# uProcesador.net
KiCad netlist of a schematic drawn in Altium Designer
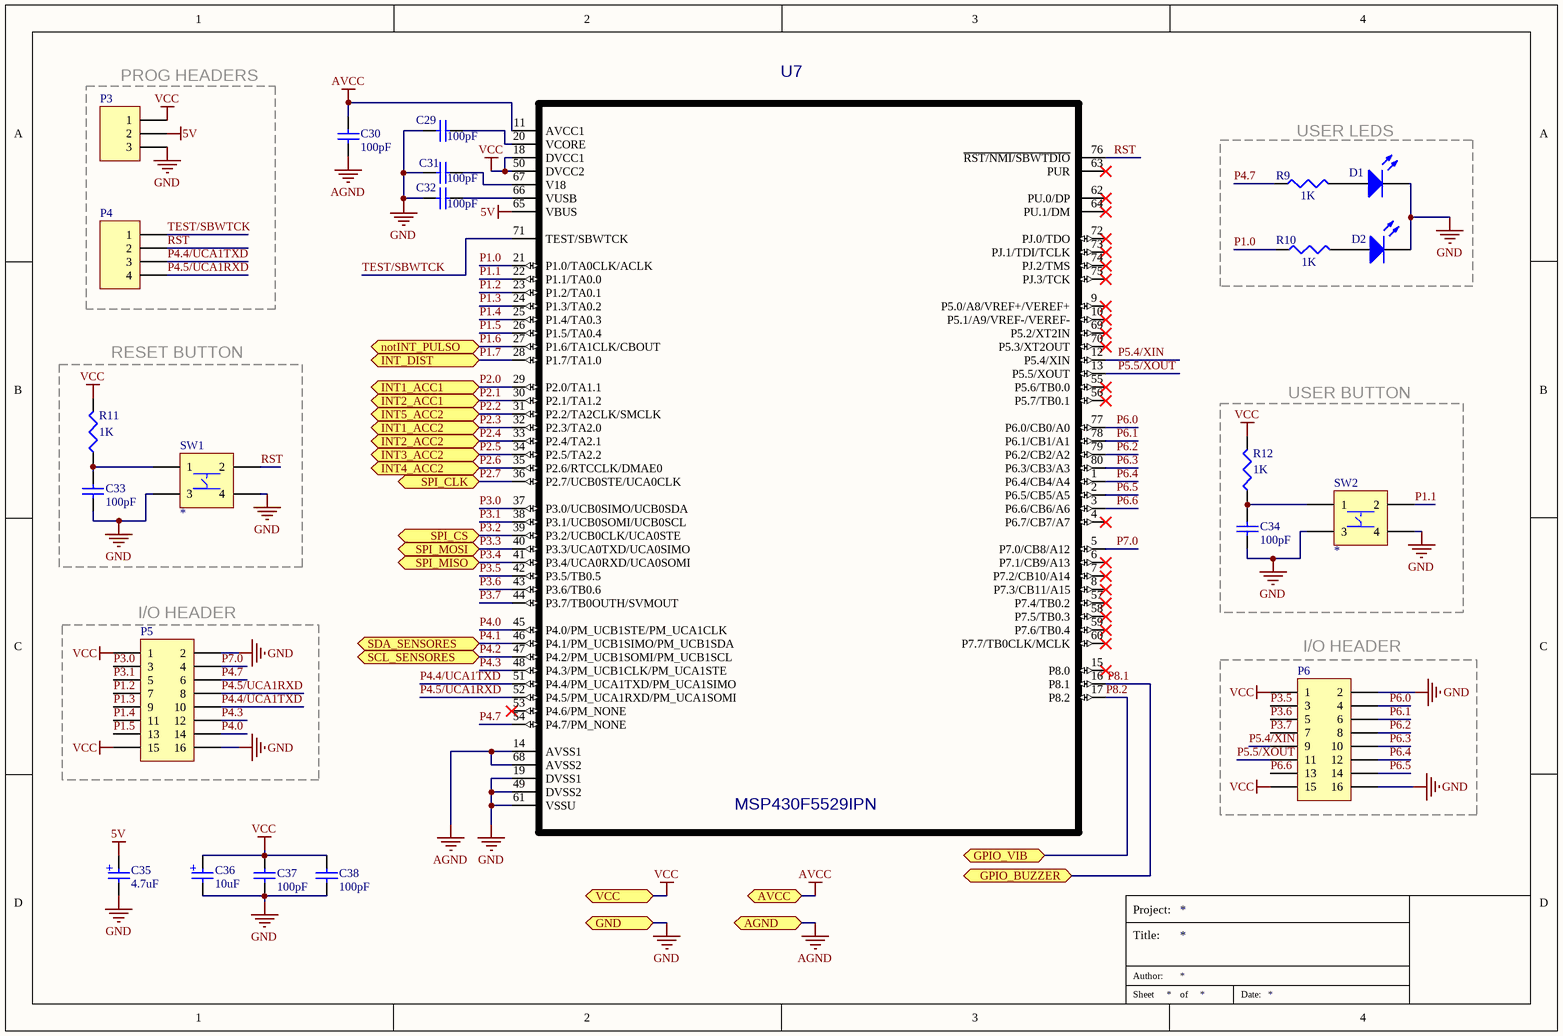
[diagram p0: uProcesador.SchDoc]

(export (version "E")
  (design (tool "Eeschema 10.0.6"))
  (components
    (comp (ref "C29")
      (value "100pF")
      (footprint "C1206")
      (description "Capacitor (Semiconductor SIM Model)")
      (fields (field (name "PUBLISHER") "Altium Limited"))
      (libsource (lib "Miscellaneous Devices") (part "Cap Semi"))
    )
    (comp (ref "C30")
      (value "100pF")
      (footprint "C1206")
      (description "Capacitor (Semiconductor SIM Model)")
      (fields (field (name "PUBLISHER") "Altium Limited"))
      (libsource (lib "Miscellaneous Devices") (part "Cap Semi"))
    )
    (comp (ref "C31")
      (value "100pF")
      (footprint "C1206")
      (description "Capacitor (Semiconductor SIM Model)")
      (fields (field (name "PUBLISHER") "Altium Limited"))
      (libsource (lib "Miscellaneous Devices") (part "Cap Semi"))
    )
    (comp (ref "C32")
      (value "100pF")
      (footprint "C1206")
      (description "Capacitor (Semiconductor SIM Model)")
      (fields (field (name "PUBLISHER") "Altium Limited"))
      (libsource (lib "Miscellaneous Devices") (part "Cap Semi"))
    )
    (comp (ref "C33")
      (value "100pF")
      (footprint "C1206")
      (description "Capacitor (Semiconductor SIM Model)")
      (fields (field (name "PUBLISHER") "Altium Limited"))
      (libsource (lib "Miscellaneous Devices") (part "Cap Semi"))
    )
    (comp (ref "C34")
      (value "100pF")
      (footprint "C1206")
      (description "Capacitor (Semiconductor SIM Model)")
      (fields (field (name "PUBLISHER") "Altium Limited"))
      (libsource (lib "Miscellaneous Devices") (part "Cap Semi"))
    )
    (comp (ref "C35")
      (value "4.7uF")
      (footprint "Cap Pol")
      (description "Capacitor pol")
      (fields (field (name "PUBLISHER") "Altium Limited"))
      (libsource (lib "Schematics") (part "Cap Pol"))
    )
    (comp (ref "C36")
      (value "10uF")
      (footprint "Cap Pol")
      (description "Capacitor pol")
      (fields (field (name "PUBLISHER") "Altium Limited"))
      (libsource (lib "Schematics") (part "Cap Pol"))
    )
    (comp (ref "C37")
      (value "100pF")
      (footprint "C1206")
      (description "Capacitor (Semiconductor SIM Model)")
      (fields (field (name "PUBLISHER") "Altium Limited"))
      (libsource (lib "Miscellaneous Devices") (part "Cap Semi"))
    )
    (comp (ref "C38")
      (value "100pF")
      (footprint "C1206")
      (description "Capacitor (Semiconductor SIM Model)")
      (fields (field (name "PUBLISHER") "Altium Limited"))
      (libsource (lib "Miscellaneous Devices") (part "Cap Semi"))
    )
    (comp (ref "D1")
      (value "~")
      (footprint "3.2X1.6X1.1")
      (description "Typical RED, GREEN, YELLOW, AMBER GaAs LED")
      (fields (field (name "PUBLISHER") "Altium Limited"))
      (libsource (lib "Miscellaneous Devices") (part "LED2"))
    )
    (comp (ref "D2")
      (value "~")
      (footprint "3.2X1.6X1.1")
      (description "Typical RED, GREEN, YELLOW, AMBER GaAs LED")
      (fields (field (name "PUBLISHER") "Altium Limited"))
      (libsource (lib "Miscellaneous Devices") (part "LED2"))
    )
    (comp (ref "P3")
      (value "~")
      (footprint "HDR1X3")
      (description "Header, 3-Pin")
      (fields (field (name "PUBLISHER") "Altium Limited"))
      (libsource (lib "Miscellaneous Connectors") (part "Header 3"))
    )
    (comp (ref "P4")
      (value "~")
      (footprint "HDR1X4")
      (description "Header, 4-Pin")
      (fields (field (name "PUBLISHER") "Altium Limited"))
      (libsource (lib "Miscellaneous Connectors") (part "Header 4"))
    )
    (comp (ref "P5")
      (value "~")
      (footprint "HDR2X8")
      (description "Header, 8-Pin, Dual row")
      (fields (field (name "PUBLISHER") "Altium Limited"))
      (libsource (lib "Miscellaneous Connectors") (part "Header 8X2"))
    )
    (comp (ref "P6")
      (value "~")
      (footprint "HDR2X8")
      (description "Header, 8-Pin, Dual row")
      (fields (field (name "PUBLISHER") "Altium Limited"))
      (libsource (lib "Miscellaneous Connectors") (part "Header 8X2"))
    )
    (comp (ref "R9")
      (value "1K")
      (footprint "J1-0603")
      (description "Resistor")
      (fields (field (name "PUBLISHER") "Altium Limited"))
      (libsource (lib "Miscellaneous Devices") (part "Res3"))
    )
    (comp (ref "R10")
      (value "1K")
      (footprint "J1-0603")
      (description "Resistor")
      (fields (field (name "PUBLISHER") "Altium Limited"))
      (libsource (lib "Miscellaneous Devices") (part "Res3"))
    )
    (comp (ref "R11")
      (value "1K")
      (footprint "J1-0603")
      (description "Resistor")
      (fields (field (name "PUBLISHER") "Altium Limited"))
      (libsource (lib "Miscellaneous Devices") (part "Res3"))
    )
    (comp (ref "R12")
      (value "1K")
      (footprint "J1-0603")
      (description "Resistor")
      (fields (field (name "PUBLISHER") "Altium Limited"))
      (libsource (lib "Miscellaneous Devices") (part "Res3"))
    )
    (comp (ref "SW1") (value "*") (footprint "CKN9085CT") (libsource (lib "Schematics") (part "CKN9085CT")))
    (comp (ref "SW2") (value "*") (footprint "CKN9085CT") (libsource (lib "Schematics") (part "CKN9085CT")))
    (comp (ref "U7")
      (value "MSP430F5529IPN")
      (footprint "QFP50P1400X1400X160-80N")
      (fields (field (name "MF") "Texas Instruments"))
      (libsource (lib "Schematics") (part "MSP430F5529IPN"))
    )
  )
  (nets
    (net (code "1") (name "/P1.0") (class "Default")
      (node (ref "R10") (pin "1") (pinfunction "1_1") (pintype "passive"))
      (node (ref "U7") (pin "21") (pinfunction "P1.0/TA0CLK/ACLK_21") (pintype "bidirectional"))
    )
    (net (code "2") (name "/P1.1") (class "Default")
      (node (ref "SW2") (pin "2") (pinfunction "2_2") (pintype "passive"))
      (node (ref "U7") (pin "22") (pinfunction "P1.1/TA0.0_22") (pintype "bidirectional"))
    )
    (net (code "3") (name "/P1.2") (class "Default")
      (node (ref "P5") (pin "7") (pinfunction "7_7") (pintype "passive"))
      (node (ref "U7") (pin "23") (pinfunction "P1.2/TA0.1_23") (pintype "bidirectional"))
    )
    (net (code "4") (name "/P1.3") (class "Default")
      (node (ref "P5") (pin "9") (pinfunction "9_9") (pintype "passive"))
      (node (ref "U7") (pin "24") (pinfunction "P1.3/TA0.2_24") (pintype "bidirectional"))
    )
    (net (code "5") (name "/P1.4") (class "Default")
      (node (ref "P5") (pin "11") (pinfunction "11_11") (pintype "passive"))
      (node (ref "U7") (pin "25") (pinfunction "P1.4/TA0.3_25") (pintype "bidirectional"))
    )
    (net (code "6") (name "/P1.5") (class "Default")
      (node (ref "P5") (pin "13") (pinfunction "13_13") (pintype "passive"))
      (node (ref "U7") (pin "26") (pinfunction "P1.5/TA0.4_26") (pintype "bidirectional"))
    )
    (net (code "7") (name "/P1.6") (class "Default")
      (node (ref "U7") (pin "27") (pinfunction "P1.6/TA1CLK/CBOUT_27") (pintype "bidirectional"))
    )
    (net (code "8") (name "/P1.7") (class "Default")
      (node (ref "U7") (pin "28") (pinfunction "P1.7/TA1.0_28") (pintype "bidirectional"))
    )
    (net (code "9") (name "/P2.0") (class "Default")
      (node (ref "U7") (pin "29") (pinfunction "P2.0/TA1.1_29") (pintype "bidirectional"))
    )
    (net (code "10") (name "/P2.1") (class "Default")
      (node (ref "U7") (pin "30") (pinfunction "P2.1/TA1.2_30") (pintype "bidirectional"))
    )
    (net (code "11") (name "/P2.2") (class "Default")
      (node (ref "U7") (pin "31") (pinfunction "P2.2/TA2CLK/SMCLK_31") (pintype "bidirectional"))
    )
    (net (code "12") (name "/P2.3") (class "Default")
      (node (ref "U7") (pin "32") (pinfunction "P2.3/TA2.0_32") (pintype "bidirectional"))
    )
    (net (code "13") (name "/P2.4") (class "Default")
      (node (ref "U7") (pin "33") (pinfunction "P2.4/TA2.1_33") (pintype "bidirectional"))
    )
    (net (code "14") (name "/P2.5") (class "Default")
      (node (ref "U7") (pin "34") (pinfunction "P2.5/TA2.2_34") (pintype "bidirectional"))
    )
    (net (code "15") (name "/P2.6") (class "Default")
      (node (ref "U7") (pin "35") (pinfunction "P2.6/RTCCLK/DMAE0_35") (pintype "bidirectional"))
    )
    (net (code "16") (name "/P2.7") (class "Default")
      (node (ref "U7") (pin "36") (pinfunction "P2.7/UCB0STE/UCA0CLK_36") (pintype "bidirectional"))
    )
    (net (code "17") (name "/P3.0") (class "Default")
      (node (ref "P5") (pin "3") (pinfunction "3_3") (pintype "passive"))
      (node (ref "U7") (pin "37") (pinfunction "P3.0/UCB0SIMO/UCB0SDA_37") (pintype "bidirectional"))
    )
    (net (code "18") (name "/P3.1") (class "Default")
      (node (ref "P5") (pin "5") (pinfunction "5_5") (pintype "passive"))
      (node (ref "U7") (pin "38") (pinfunction "P3.1/UCB0SOMI/UCB0SCL_38") (pintype "bidirectional"))
    )
    (net (code "19") (name "/P3.2") (class "Default")
      (node (ref "U7") (pin "39") (pinfunction "P3.2/UCB0CLK/UCA0STE_39") (pintype "bidirectional"))
    )
    (net (code "20") (name "/P3.3") (class "Default")
      (node (ref "U7") (pin "40") (pinfunction "P3.3/UCA0TXD/UCA0SIMO_40") (pintype "bidirectional"))
    )
    (net (code "21") (name "/P3.4") (class "Default")
      (node (ref "U7") (pin "41") (pinfunction "P3.4/UCA0RXD/UCA0SOMI_41") (pintype "bidirectional"))
    )
    (net (code "22") (name "/P3.5") (class "Default")
      (node (ref "P6") (pin "3") (pinfunction "3_3") (pintype "passive"))
      (node (ref "U7") (pin "42") (pinfunction "P3.5/TB0.5_42") (pintype "bidirectional"))
    )
    (net (code "23") (name "/P3.6") (class "Default")
      (node (ref "P6") (pin "5") (pinfunction "5_5") (pintype "passive"))
      (node (ref "U7") (pin "43") (pinfunction "P3.6/TB0.6_43") (pintype "bidirectional"))
    )
    (net (code "24") (name "/P3.7") (class "Default")
      (node (ref "P6") (pin "7") (pinfunction "7_7") (pintype "passive"))
      (node (ref "U7") (pin "44") (pinfunction "P3.7/TB0OUTH/SVMOUT_44") (pintype "bidirectional"))
    )
    (net (code "25") (name "/P4.0") (class "Default")
      (node (ref "P5") (pin "14") (pinfunction "14_14") (pintype "passive"))
      (node (ref "U7") (pin "45") (pinfunction "P4.0/PM_UCB1STE/PM_UCA1CLK_45") (pintype "bidirectional"))
    )
    (net (code "26") (name "/P4.1") (class "Default")
      (node (ref "U7") (pin "46") (pinfunction "P4.1/PM_UCB1SIMO/PM_UCB1SDA_46") (pintype "bidirectional"))
    )
    (net (code "27") (name "/P4.2") (class "Default")
      (node (ref "U7") (pin "47") (pinfunction "P4.2/PM_UCB1SOMI/PM_UCB1SCL_47") (pintype "bidirectional"))
    )
    (net (code "28") (name "/P4.3") (class "Default")
      (node (ref "P5") (pin "12") (pinfunction "12_12") (pintype "passive"))
      (node (ref "U7") (pin "48") (pinfunction "P4.3/PM_UCB1CLK/PM_UCA1STE_48") (pintype "bidirectional"))
    )
    (net (code "29") (name "/P4.4{slash}UCA1TXD") (class "Default")
      (node (ref "P4") (pin "3") (pinfunction "3_3") (pintype "passive"))
      (node (ref "P5") (pin "10") (pinfunction "10_10") (pintype "passive"))
      (node (ref "U7") (pin "51") (pinfunction "P4.4/PM_UCA1TXD/PM_UCA1SIMO_51") (pintype "bidirectional"))
    )
    (net (code "30") (name "/P4.5{slash}UCA1RXD") (class "Default")
      (node (ref "P4") (pin "4") (pinfunction "4_4") (pintype "passive"))
      (node (ref "P5") (pin "8") (pinfunction "8_8") (pintype "passive"))
      (node (ref "U7") (pin "52") (pinfunction "P4.5/PM_UCA1RXD/PM_UCA1SOMI_52") (pintype "bidirectional"))
    )
    (net (code "31") (name "/P4.7") (class "Default")
      (node (ref "P5") (pin "6") (pinfunction "6_6") (pintype "passive"))
      (node (ref "R9") (pin "1") (pinfunction "1_1") (pintype "passive"))
      (node (ref "U7") (pin "54") (pinfunction "P4.7/PM_NONE_54") (pintype "bidirectional"))
    )
    (net (code "32") (name "/P5.4{slash}XIN") (class "Default")
      (node (ref "P6") (pin "9") (pinfunction "9_9") (pintype "passive"))
      (node (ref "U7") (pin "12") (pinfunction "P5.4/XIN_12") (pintype "bidirectional"))
    )
    (net (code "33") (name "/P5.5{slash}XOUT") (class "Default")
      (node (ref "P6") (pin "11") (pinfunction "11_11") (pintype "passive"))
      (node (ref "U7") (pin "13") (pinfunction "P5.5/XOUT_13") (pintype "bidirectional"))
    )
    (net (code "34") (name "/P6.0") (class "Default")
      (node (ref "P6") (pin "4") (pinfunction "4_4") (pintype "passive"))
      (node (ref "U7") (pin "77") (pinfunction "P6.0/CB0/A0_77") (pintype "bidirectional"))
    )
    (net (code "35") (name "/P6.1") (class "Default")
      (node (ref "P6") (pin "6") (pinfunction "6_6") (pintype "passive"))
      (node (ref "U7") (pin "78") (pinfunction "P6.1/CB1/A1_78") (pintype "bidirectional"))
    )
    (net (code "36") (name "/P6.2") (class "Default")
      (node (ref "P6") (pin "8") (pinfunction "8_8") (pintype "passive"))
      (node (ref "U7") (pin "79") (pinfunction "P6.2/CB2/A2_79") (pintype "bidirectional"))
    )
    (net (code "37") (name "/P6.3") (class "Default")
      (node (ref "P6") (pin "10") (pinfunction "10_10") (pintype "passive"))
      (node (ref "U7") (pin "80") (pinfunction "P6.3/CB3/A3_80") (pintype "bidirectional"))
    )
    (net (code "38") (name "/P6.4") (class "Default")
      (node (ref "P6") (pin "12") (pinfunction "12_12") (pintype "passive"))
      (node (ref "U7") (pin "1") (pinfunction "P6.4/CB4/A4_1") (pintype "bidirectional"))
    )
    (net (code "39") (name "/P6.5") (class "Default")
      (node (ref "P6") (pin "14") (pinfunction "14_14") (pintype "passive"))
      (node (ref "U7") (pin "2") (pinfunction "P6.5/CB5/A5_2") (pintype "bidirectional"))
    )
    (net (code "40") (name "/P6.6") (class "Default")
      (node (ref "P6") (pin "13") (pinfunction "13_13") (pintype "passive"))
      (node (ref "U7") (pin "3") (pinfunction "P6.6/CB6/A6_3") (pintype "bidirectional"))
    )
    (net (code "41") (name "/P7.0") (class "Default")
      (node (ref "P5") (pin "4") (pinfunction "4_4") (pintype "passive"))
      (node (ref "U7") (pin "5") (pinfunction "P7.0/CB8/A12_5") (pintype "bidirectional"))
    )
    (net (code "42") (name "/P8.1") (class "Default")
      (node (ref "U7") (pin "16") (pinfunction "P8.1_16") (pintype "bidirectional"))
    )
    (net (code "43") (name "/P8.2") (class "Default")
      (node (ref "U7") (pin "17") (pinfunction "P8.2_17") (pintype "bidirectional"))
    )
    (net (code "44") (name "/RST") (class "Default")
      (node (ref "P4") (pin "2") (pinfunction "2_2") (pintype "passive"))
      (node (ref "SW1") (pin "2") (pinfunction "2_2") (pintype "passive"))
      (node (ref "U7") (pin "76") (pinfunction "~{RST/NMI/SBWTDIO}_76") (pintype "passive"))
    )
    (net (code "45") (name "/TEST{slash}SBWTCK") (class "Default")
      (node (ref "P4") (pin "1") (pinfunction "1_1") (pintype "passive"))
      (node (ref "U7") (pin "71") (pinfunction "TEST/SBWTCK_71") (pintype "passive"))
    )
    (net (code "46") (name "5V") (class "Default")
      (node (ref "C35") (pin "2") (pinfunction "2_2") (pintype "passive"))
      (node (ref "P3") (pin "2") (pinfunction "2_2") (pintype "passive"))
      (node (ref "U7") (pin "65") (pinfunction "VBUS_65") (pintype "passive"))
    )
    (net (code "47") (name "AGND") (class "Default")
      (node (ref "C30") (pin "1") (pinfunction "1_1") (pintype "passive"))
      (node (ref "U7") (pin "14") (pinfunction "AVSS1_14") (pintype "power_in"))
      (node (ref "U7") (pin "68") (pinfunction "AVSS2_68") (pintype "power_in"))
    )
    (net (code "48") (name "AVCC") (class "Default")
      (node (ref "C30") (pin "2") (pinfunction "2_2") (pintype "passive"))
      (node (ref "U7") (pin "11") (pinfunction "AVCC1_11") (pintype "power_in"))
    )
    (net (code "49") (name "GND") (class "Default")
      (node (ref "C29") (pin "2") (pinfunction "2_2") (pintype "passive"))
      (node (ref "C31") (pin "2") (pinfunction "2_2") (pintype "passive"))
      (node (ref "C32") (pin "2") (pinfunction "2_2") (pintype "passive"))
      (node (ref "C33") (pin "1") (pinfunction "1_1") (pintype "passive"))
      (node (ref "C34") (pin "1") (pinfunction "1_1") (pintype "passive"))
      (node (ref "C35") (pin "1") (pinfunction "1_1") (pintype "passive"))
      (node (ref "C36") (pin "1") (pinfunction "1_1") (pintype "passive"))
      (node (ref "C37") (pin "1") (pinfunction "1_1") (pintype "passive"))
      (node (ref "C38") (pin "1") (pinfunction "1_1") (pintype "passive"))
      (node (ref "D1") (pin "2") (pinfunction "K_2") (pintype "passive"))
      (node (ref "D2") (pin "2") (pinfunction "K_2") (pintype "passive"))
      (node (ref "P3") (pin "3") (pinfunction "3_3") (pintype "passive"))
      (node (ref "P5") (pin "16") (pinfunction "16_16") (pintype "passive"))
      (node (ref "P5") (pin "2") (pinfunction "2_2") (pintype "passive"))
      (node (ref "P6") (pin "16") (pinfunction "16_16") (pintype "passive"))
      (node (ref "P6") (pin "2") (pinfunction "2_2") (pintype "passive"))
      (node (ref "SW1") (pin "3") (pinfunction "3_3") (pintype "passive"))
      (node (ref "SW1") (pin "4") (pinfunction "4_4") (pintype "passive"))
      (node (ref "SW2") (pin "3") (pinfunction "3_3") (pintype "passive"))
      (node (ref "SW2") (pin "4") (pinfunction "4_4") (pintype "passive"))
      (node (ref "U7") (pin "19") (pinfunction "DVSS1_19") (pintype "power_in"))
      (node (ref "U7") (pin "49") (pinfunction "DVSS2_49") (pintype "power_in"))
      (node (ref "U7") (pin "61") (pinfunction "VSSU_61") (pintype "power_in"))
    )
    (net (code "50") (name "Net-(C33-Pad2)") (class "Default")
      (node (ref "C33") (pin "2") (pinfunction "2_2") (pintype "passive"))
      (node (ref "R11") (pin "1") (pinfunction "1_1") (pintype "passive"))
      (node (ref "SW1") (pin "1") (pinfunction "1_1") (pintype "passive"))
    )
    (net (code "51") (name "Net-(C34-Pad2)") (class "Default")
      (node (ref "C34") (pin "2") (pinfunction "2_2") (pintype "passive"))
      (node (ref "R12") (pin "1") (pinfunction "1_1") (pintype "passive"))
      (node (ref "SW2") (pin "1") (pinfunction "1_1") (pintype "passive"))
    )
    (net (code "52") (name "Net-(D1-A)") (class "Default")
      (node (ref "D1") (pin "1") (pinfunction "A_1") (pintype "passive"))
      (node (ref "R9") (pin "2") (pinfunction "2_2") (pintype "passive"))
    )
    (net (code "53") (name "Net-(D2-A)") (class "Default")
      (node (ref "D2") (pin "1") (pinfunction "A_1") (pintype "passive"))
      (node (ref "R10") (pin "2") (pinfunction "2_2") (pintype "passive"))
    )
    (net (code "54") (name "Net-(U7-V18)") (class "Default")
      (node (ref "C31") (pin "1") (pinfunction "1_1") (pintype "passive"))
      (node (ref "U7") (pin "67") (pinfunction "V18_67") (pintype "passive"))
    )
    (net (code "55") (name "Net-(U7-VCORE)") (class "Default")
      (node (ref "C29") (pin "1") (pinfunction "1_1") (pintype "passive"))
      (node (ref "U7") (pin "20") (pinfunction "VCORE_20") (pintype "passive"))
    )
    (net (code "56") (name "Net-(U7-VUSB)") (class "Default")
      (node (ref "C32") (pin "1") (pinfunction "1_1") (pintype "passive"))
      (node (ref "U7") (pin "66") (pinfunction "VUSB_66") (pintype "passive"))
    )
    (net (code "57") (name "VCC") (class "Default")
      (node (ref "C36") (pin "2") (pinfunction "2_2") (pintype "passive"))
      (node (ref "C37") (pin "2") (pinfunction "2_2") (pintype "passive"))
      (node (ref "C38") (pin "2") (pinfunction "2_2") (pintype "passive"))
      (node (ref "P3") (pin "1") (pinfunction "1_1") (pintype "passive"))
      (node (ref "P5") (pin "1") (pinfunction "1_1") (pintype "passive"))
      (node (ref "P5") (pin "15") (pinfunction "15_15") (pintype "passive"))
      (node (ref "P6") (pin "1") (pinfunction "1_1") (pintype "passive"))
      (node (ref "P6") (pin "15") (pinfunction "15_15") (pintype "passive"))
      (node (ref "R11") (pin "2") (pinfunction "2_2") (pintype "passive"))
      (node (ref "R12") (pin "2") (pinfunction "2_2") (pintype "passive"))
      (node (ref "U7") (pin "18") (pinfunction "DVCC1_18") (pintype "power_in"))
      (node (ref "U7") (pin "50") (pinfunction "DVCC2_50") (pintype "power_in"))
    )
    (net (code "58") (name "unconnected-(U7-P4.6{slash}PM_NONE-Pad53)") (class "Default")
      (node (ref "U7") (pin "53") (pinfunction "P4.6/PM_NONE_53") (pintype "bidirectional+no_connect"))
    )
    (net (code "59") (name "unconnected-(U7-P5.0{slash}A8{slash}VREF+{slash}VEREF+-Pad9)") (class "Default")
      (node (ref "U7") (pin "9") (pinfunction "P5.0/A8/VREF+/VEREF+_9") (pintype "bidirectional+no_connect"))
    )
    (net (code "60") (name "unconnected-(U7-P5.1{slash}A9{slash}VREF-{slash}VEREF--Pad10)") (class "Default")
      (node (ref "U7") (pin "10") (pinfunction "P5.1/A9/VREF-/VEREF-_10") (pintype "bidirectional+no_connect"))
    )
    (net (code "61") (name "unconnected-(U7-P5.2{slash}XT2IN-Pad69)") (class "Default")
      (node (ref "U7") (pin "69") (pinfunction "P5.2/XT2IN_69") (pintype "bidirectional+no_connect"))
    )
    (net (code "62") (name "unconnected-(U7-P5.3{slash}XT2OUT-Pad70)") (class "Default")
      (node (ref "U7") (pin "70") (pinfunction "P5.3/XT2OUT_70") (pintype "bidirectional+no_connect"))
    )
    (net (code "63") (name "unconnected-(U7-P5.6{slash}TB0.0-Pad55)") (class "Default")
      (node (ref "U7") (pin "55") (pinfunction "P5.6/TB0.0_55") (pintype "bidirectional+no_connect"))
    )
    (net (code "64") (name "unconnected-(U7-P5.7{slash}TB0.1-Pad56)") (class "Default")
      (node (ref "U7") (pin "56") (pinfunction "P5.7/TB0.1_56") (pintype "bidirectional+no_connect"))
    )
    (net (code "65") (name "unconnected-(U7-P6.7{slash}CB7{slash}A7-Pad4)") (class "Default")
      (node (ref "U7") (pin "4") (pinfunction "P6.7/CB7/A7_4") (pintype "bidirectional+no_connect"))
    )
    (net (code "66") (name "unconnected-(U7-P7.1{slash}CB9{slash}A13-Pad6)") (class "Default")
      (node (ref "U7") (pin "6") (pinfunction "P7.1/CB9/A13_6") (pintype "bidirectional+no_connect"))
    )
    (net (code "67") (name "unconnected-(U7-P7.2{slash}CB10{slash}A14-Pad7)") (class "Default")
      (node (ref "U7") (pin "7") (pinfunction "P7.2/CB10/A14_7") (pintype "bidirectional+no_connect"))
    )
    (net (code "68") (name "unconnected-(U7-P7.3{slash}CB11{slash}A15-Pad8)") (class "Default")
      (node (ref "U7") (pin "8") (pinfunction "P7.3/CB11/A15_8") (pintype "bidirectional+no_connect"))
    )
    (net (code "69") (name "unconnected-(U7-P7.4{slash}TB0.2-Pad57)") (class "Default")
      (node (ref "U7") (pin "57") (pinfunction "P7.4/TB0.2_57") (pintype "bidirectional+no_connect"))
    )
    (net (code "70") (name "unconnected-(U7-P7.5{slash}TB0.3-Pad58)") (class "Default")
      (node (ref "U7") (pin "58") (pinfunction "P7.5/TB0.3_58") (pintype "bidirectional+no_connect"))
    )
    (net (code "71") (name "unconnected-(U7-P7.6{slash}TB0.4-Pad59)") (class "Default")
      (node (ref "U7") (pin "59") (pinfunction "P7.6/TB0.4_59") (pintype "bidirectional+no_connect"))
    )
    (net (code "72") (name "unconnected-(U7-P7.7{slash}TB0CLK{slash}MCLK-Pad60)") (class "Default")
      (node (ref "U7") (pin "60") (pinfunction "P7.7/TB0CLK/MCLK_60") (pintype "bidirectional+no_connect"))
    )
    (net (code "73") (name "unconnected-(U7-P8.0-Pad15)") (class "Default")
      (node (ref "U7") (pin "15") (pinfunction "P8.0_15") (pintype "bidirectional+no_connect"))
    )
    (net (code "74") (name "unconnected-(U7-PJ.0{slash}TDO-Pad72)") (class "Default")
      (node (ref "U7") (pin "72") (pinfunction "PJ.0/TDO_72") (pintype "bidirectional+no_connect"))
    )
    (net (code "75") (name "unconnected-(U7-PJ.1{slash}TDI{slash}TCLK-Pad73)") (class "Default")
      (node (ref "U7") (pin "73") (pinfunction "PJ.1/TDI/TCLK_73") (pintype "bidirectional+no_connect"))
    )
    (net (code "76") (name "unconnected-(U7-PJ.2{slash}TMS-Pad74)") (class "Default")
      (node (ref "U7") (pin "74") (pinfunction "PJ.2/TMS_74") (pintype "bidirectional+no_connect"))
    )
    (net (code "77") (name "unconnected-(U7-PJ.3{slash}TCK-Pad75)") (class "Default")
      (node (ref "U7") (pin "75") (pinfunction "PJ.3/TCK_75") (pintype "bidirectional+no_connect"))
    )
    (net (code "78") (name "unconnected-(U7-PU.0{slash}DP-Pad62)") (class "Default")
      (node (ref "U7") (pin "62") (pinfunction "PU.0/DP_62") (pintype "passive+no_connect"))
    )
    (net (code "79") (name "unconnected-(U7-PU.1{slash}DM-Pad64)") (class "Default")
      (node (ref "U7") (pin "64") (pinfunction "PU.1/DM_64") (pintype "passive+no_connect"))
    )
    (net (code "80") (name "unconnected-(U7-PUR-Pad63)") (class "Default")
      (node (ref "U7") (pin "63") (pinfunction "PUR_63") (pintype "passive+no_connect"))
    )
  )
)
